# SH7_-_SD_CARD_CONNECTOR.net
KiCad netlist of a schematic drawn in Altium Designer
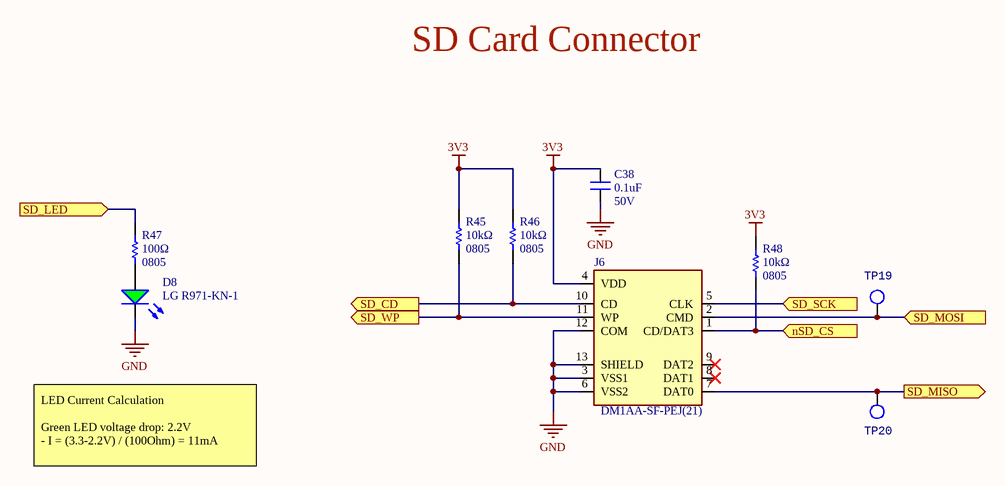
[diagram p0: SH7 - SD CARD CONNECTOR.SchDoc]

(export (version "E")
  (design (tool "Eeschema 10.0.6"))
  (components
    (comp (ref "C38")
      (value "0.1uF")
      (footprint "CAPC2012X140N")
      (description "CAP CER 0.1UF 50V X7R 0805")
      (fields
        (field (name "TOLERANCE") "10%")
        (field (name "VOLTAGE RATING") "50V")
        (field (name "Comment") "CAP_0.1uF_50V_0805")
      )
      (libsource (lib "UWRT_Schematic_Library_2020") (part "CAP_0.1uF_50V_0805"))
    )
    (comp (ref "D8")
      (value "DIO_LED_G")
      (footprint "LED_0805_LINE")
      (description "LED GREEN DIFFUSED 0805 SMD")
      (fields (field (name "MANUFACTURER PART NUMBER 1") "LG R971-KN-1"))
      (libsource (lib "UWRT_Schematic_Library_2020") (part "DIO_LED_G"))
    )
    (comp (ref "J6")
      (value "SD_CARD_CON")
      (footprint "HRS_DM1AA-SF-PEJ(21)")
      (description "12 _9 + 3_ Position Card Connector Secure Digital - SD Surface Mount, Right Angle Gold")
      (fields (field (name "MANUFACTURER PART NUMBER 1") "DM1AA-SF-PEJ(21)"))
      (libsource (lib "UWRT_Schematic_Library_2020") (part "SD_CARD_CON"))
    )
    (comp (ref "R45")
      (value "10kΩ")
      (footprint "RESC2012X60N")
      (description "RES SMD 10K OHM 1% 1/8W 0805")
      (fields
        (field (name "CASE CODE (IMPERIAL)") "0805")
        (field (name "TOLERANCE") "1%")
        (field (name "Comment") "RES_10kΩ_0805")
      )
      (libsource (lib "UWRT_Schematic_Library_2020") (part "RES_10kΩ_0805"))
    )
    (comp (ref "R46")
      (value "10kΩ")
      (footprint "RESC2012X60N")
      (description "RES SMD 10K OHM 1% 1/8W 0805")
      (fields
        (field (name "CASE CODE (IMPERIAL)") "0805")
        (field (name "TOLERANCE") "1%")
        (field (name "Comment") "RES_10kΩ_0805")
      )
      (libsource (lib "UWRT_Schematic_Library_2020") (part "RES_10kΩ_0805"))
    )
    (comp (ref "R47")
      (value "100Ω")
      (footprint "RESC2012X60N")
      (description "RES SMD 100 OHM 1% 1/8W 0805")
      (fields (field (name "CASE CODE (IMPERIAL)") "0805") (field (name "Comment") "RES_100Ω_0805"))
      (libsource (lib "UWRT_Schematic_Library_2020") (part "RES_100Ω_0805"))
    )
    (comp (ref "R48")
      (value "10kΩ")
      (footprint "RESC2012X60N")
      (description "RES SMD 10K OHM 1% 1/8W 0805")
      (fields
        (field (name "CASE CODE (IMPERIAL)") "0805")
        (field (name "TOLERANCE") "1%")
        (field (name "Comment") "RES_10kΩ_0805")
      )
      (libsource (lib "UWRT_Schematic_Library_2020") (part "RES_10kΩ_0805"))
    )
    (comp (ref "TP19")
      (value "TESTPOINT_LOOP")
      (footprint "TESTPOINT_LOOP")
      (description "Loop testpoint through-hole pad")
      (libsource (lib "UWRT_Schematic_Library_2020") (part "TESTPOINT_LOOP"))
    )
    (comp (ref "TP20")
      (value "TESTPOINT_LOOP")
      (footprint "TESTPOINT_LOOP")
      (description "Loop testpoint through-hole pad")
      (libsource (lib "UWRT_Schematic_Library_2020") (part "TESTPOINT_LOOP"))
    )
  )
  (nets
    (net (code "1") (name "/SD_CD") (class "Default")
      (node (ref "J6") (pin "10") (pinfunction "CD_10") (pintype "passive"))
      (node (ref "R46") (pin "1") (pinfunction "1_1") (pintype "passive"))
    )
    (net (code "2") (name "/SD_LED") (class "Default")
      (node (ref "R47") (pin "2") (pinfunction "2_2") (pintype "passive"))
    )
    (net (code "3") (name "/SD_MISO") (class "Default")
      (node (ref "J6") (pin "7") (pinfunction "DAT0_7") (pintype "passive"))
      (node (ref "TP20") (pin "1") (pintype "passive"))
    )
    (net (code "4") (name "/SD_MOSI") (class "Default")
      (node (ref "J6") (pin "2") (pinfunction "CMD_2") (pintype "passive"))
      (node (ref "TP19") (pin "1") (pintype "passive"))
    )
    (net (code "5") (name "/SD_SCK") (class "Default")
      (node (ref "J6") (pin "5") (pinfunction "CLK_5") (pintype "passive"))
    )
    (net (code "6") (name "/SD_WP") (class "Default")
      (node (ref "J6") (pin "11") (pinfunction "WP_11") (pintype "passive"))
      (node (ref "R45") (pin "1") (pinfunction "1_1") (pintype "passive"))
    )
    (net (code "7") (name "/nSD_CS") (class "Default")
      (node (ref "J6") (pin "1") (pinfunction "CD/DAT3_1") (pintype "passive"))
      (node (ref "R48") (pin "1") (pinfunction "1_1") (pintype "passive"))
    )
    (net (code "8") (name "3V3") (class "Default")
      (node (ref "C38") (pin "2") (pinfunction "2_2") (pintype "passive"))
      (node (ref "J6") (pin "4") (pinfunction "VDD_4") (pintype "power_in"))
      (node (ref "R45") (pin "2") (pinfunction "2_2") (pintype "passive"))
      (node (ref "R46") (pin "2") (pinfunction "2_2") (pintype "passive"))
      (node (ref "R48") (pin "2") (pinfunction "2_2") (pintype "passive"))
    )
    (net (code "9") (name "GND") (class "Default")
      (node (ref "C38") (pin "1") (pinfunction "1_1") (pintype "passive"))
      (node (ref "D8") (pin "2") (pinfunction "K_2") (pintype "passive"))
      (node (ref "J6") (pin "12") (pinfunction "COM_12") (pintype "passive"))
      (node (ref "J6") (pin "13") (pinfunction "SHIELD_13") (pintype "passive"))
      (node (ref "J6") (pin "3") (pinfunction "VSS1_3") (pintype "power_in"))
      (node (ref "J6") (pin "6") (pinfunction "VSS2_6") (pintype "power_in"))
    )
    (net (code "10") (name "Net-(D8-A)") (class "Default")
      (node (ref "D8") (pin "1") (pinfunction "A_1") (pintype "passive"))
      (node (ref "R47") (pin "1") (pinfunction "1_1") (pintype "passive"))
    )
    (net (code "11") (name "unconnected-(J6-DAT1-Pad8)") (class "Default")
      (node (ref "J6") (pin "8") (pinfunction "DAT1_8") (pintype "passive+no_connect"))
    )
    (net (code "12") (name "unconnected-(J6-DAT2-Pad9)") (class "Default")
      (node (ref "J6") (pin "9") (pinfunction "DAT2_9") (pintype "passive+no_connect"))
    )
  )
)
